# Sheet1_1.net
KiCad netlist of a schematic drawn in Altium Designer
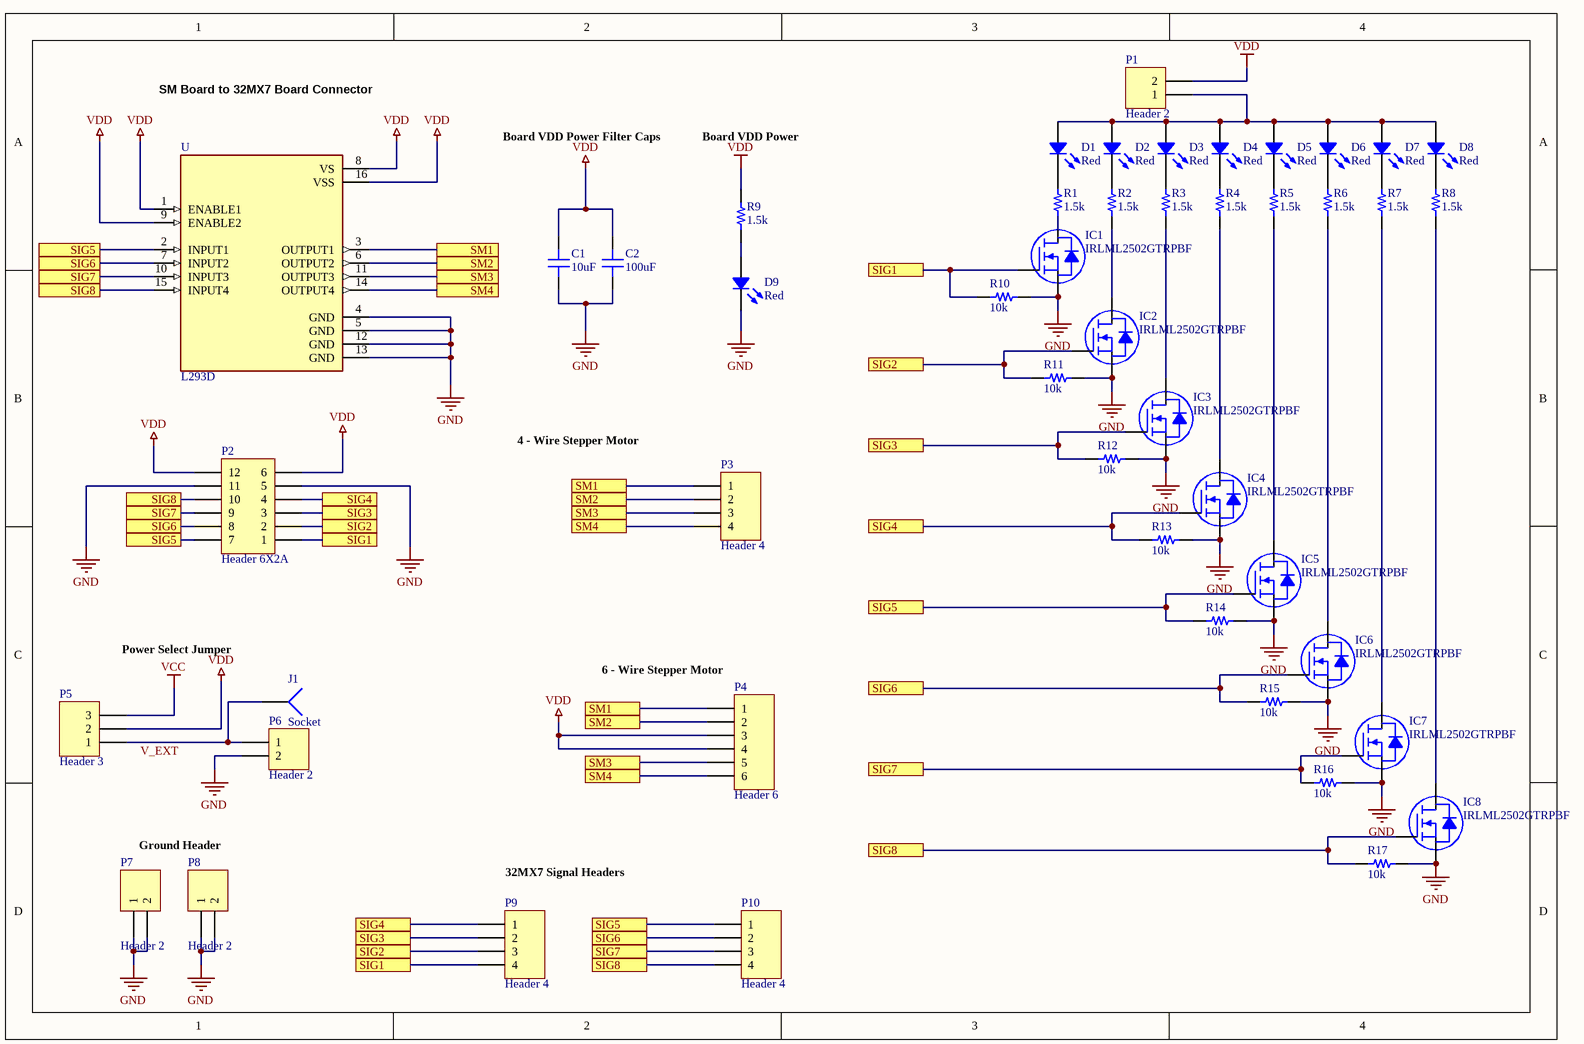
[diagram p0: Sheet1 (1).SchDoc]

(export (version "E")
  (design (tool "Eeschema 10.0.6"))
  (components
    (comp (ref "C1")
      (value "10uF")
      (footprint "CAP 1206/3216")
      (description "CAP CER 10UF 16V X5R 1206")
      (fields
        (field (name "PART NUMBER") "CL31A106KOCLNNC")
        (field (name "MANUFACTURER") "Samsung Electro-Mechanics America, Inc.")
      )
      (libsource (lib "Capacitor - Ceramic - Sumsung") (part "CL31A106KOCLNNC"))
    )
    (comp (ref "C2")
      (value "100uF")
      (footprint "CAP 1206/3216")
      (description "CAP CER 100UF 6.3V X5R 1206")
      (fields
        (field (name "PART NUMBER") "CL31A107MQHNNNE")
        (field (name "MANUFACTURER") "Samsung Electro-Mechanics America, Inc.")
      )
      (libsource (lib "Capacitor - Ceramic - Sumsung") (part "CL31A107MQHNNNE"))
    )
    (comp (ref "D1")
      (value "Red")
      (footprint "LED 1206/3216 RED")
      (description "LED RED CLEAR 1206 SMD")
      (fields (field (name "PART NUMBER") "SM1206NHC-IL") (field (name "MANUFACTURER") "Bivar Inc."))
      (libsource (lib "Chip LED") (part "SM1206NHC-IL"))
    )
    (comp (ref "D2")
      (value "Red")
      (footprint "LED 1206/3216 RED")
      (description "LED RED CLEAR 1206 SMD")
      (fields (field (name "PART NUMBER") "SM1206NHC-IL") (field (name "MANUFACTURER") "Bivar Inc."))
      (libsource (lib "Chip LED") (part "SM1206NHC-IL"))
    )
    (comp (ref "D3")
      (value "Red")
      (footprint "LED 1206/3216 RED")
      (description "LED RED CLEAR 1206 SMD")
      (fields (field (name "PART NUMBER") "SM1206NHC-IL") (field (name "MANUFACTURER") "Bivar Inc."))
      (libsource (lib "Chip LED") (part "SM1206NHC-IL"))
    )
    (comp (ref "D4")
      (value "Red")
      (footprint "LED 1206/3216 RED")
      (description "LED RED CLEAR 1206 SMD")
      (fields (field (name "PART NUMBER") "SM1206NHC-IL") (field (name "MANUFACTURER") "Bivar Inc."))
      (libsource (lib "Chip LED") (part "SM1206NHC-IL"))
    )
    (comp (ref "D5")
      (value "Red")
      (footprint "LED 1206/3216 RED")
      (description "LED RED CLEAR 1206 SMD")
      (fields (field (name "PART NUMBER") "SM1206NHC-IL") (field (name "MANUFACTURER") "Bivar Inc."))
      (libsource (lib "Chip LED") (part "SM1206NHC-IL"))
    )
    (comp (ref "D6")
      (value "Red")
      (footprint "LED 1206/3216 RED")
      (description "LED RED CLEAR 1206 SMD")
      (fields (field (name "PART NUMBER") "SM1206NHC-IL") (field (name "MANUFACTURER") "Bivar Inc."))
      (libsource (lib "Chip LED") (part "SM1206NHC-IL"))
    )
    (comp (ref "D7")
      (value "Red")
      (footprint "LED 1206/3216 RED")
      (description "LED RED CLEAR 1206 SMD")
      (fields (field (name "PART NUMBER") "SM1206NHC-IL") (field (name "MANUFACTURER") "Bivar Inc."))
      (libsource (lib "Chip LED") (part "SM1206NHC-IL"))
    )
    (comp (ref "D8")
      (value "Red")
      (footprint "LED 1206/3216 RED")
      (description "LED RED CLEAR 1206 SMD")
      (fields (field (name "PART NUMBER") "SM1206NHC-IL") (field (name "MANUFACTURER") "Bivar Inc."))
      (libsource (lib "Chip LED") (part "SM1206NHC-IL"))
    )
    (comp (ref "D9")
      (value "Red")
      (footprint "LED 1206/3216 RED")
      (description "LED RED CLEAR 1206 SMD")
      (fields (field (name "PART NUMBER") "SM1206NHC-IL") (field (name "MANUFACTURER") "Bivar Inc."))
      (libsource (lib "Chip LED") (part "SM1206NHC-IL"))
    )
    (comp (ref "IC1")
      (value "IRLML2502GTRPBF")
      (footprint "INFINEON SOT-23-3")
      (description "MOSFET N-CH 20V 4.2A SOT-23-3")
      (fields (field (name "MANUFACTURER") "Infineon Technologies"))
      (libsource (lib "N-Channel FET") (part "IRLML2502GTRPBF"))
    )
    (comp (ref "IC2")
      (value "IRLML2502GTRPBF")
      (footprint "INFINEON SOT-23-3")
      (description "MOSFET N-CH 20V 4.2A SOT-23-3")
      (fields (field (name "MANUFACTURER") "Infineon Technologies"))
      (libsource (lib "N-Channel FET") (part "IRLML2502GTRPBF"))
    )
    (comp (ref "IC3")
      (value "IRLML2502GTRPBF")
      (footprint "INFINEON SOT-23-3")
      (description "MOSFET N-CH 20V 4.2A SOT-23-3")
      (fields (field (name "MANUFACTURER") "Infineon Technologies"))
      (libsource (lib "N-Channel FET") (part "IRLML2502GTRPBF"))
    )
    (comp (ref "IC4")
      (value "IRLML2502GTRPBF")
      (footprint "INFINEON SOT-23-3")
      (description "MOSFET N-CH 20V 4.2A SOT-23-3")
      (fields (field (name "MANUFACTURER") "Infineon Technologies"))
      (libsource (lib "N-Channel FET") (part "IRLML2502GTRPBF"))
    )
    (comp (ref "IC5")
      (value "IRLML2502GTRPBF")
      (footprint "INFINEON SOT-23-3")
      (description "MOSFET N-CH 20V 4.2A SOT-23-3")
      (fields (field (name "MANUFACTURER") "Infineon Technologies"))
      (libsource (lib "N-Channel FET") (part "IRLML2502GTRPBF"))
    )
    (comp (ref "IC6")
      (value "IRLML2502GTRPBF")
      (footprint "INFINEON SOT-23-3")
      (description "MOSFET N-CH 20V 4.2A SOT-23-3")
      (fields (field (name "MANUFACTURER") "Infineon Technologies"))
      (libsource (lib "N-Channel FET") (part "IRLML2502GTRPBF"))
    )
    (comp (ref "IC7")
      (value "IRLML2502GTRPBF")
      (footprint "INFINEON SOT-23-3")
      (description "MOSFET N-CH 20V 4.2A SOT-23-3")
      (fields (field (name "MANUFACTURER") "Infineon Technologies"))
      (libsource (lib "N-Channel FET") (part "IRLML2502GTRPBF"))
    )
    (comp (ref "IC8")
      (value "IRLML2502GTRPBF")
      (footprint "INFINEON SOT-23-3")
      (description "MOSFET N-CH 20V 4.2A SOT-23-3")
      (fields (field (name "MANUFACTURER") "Infineon Technologies"))
      (libsource (lib "N-Channel FET") (part "IRLML2502GTRPBF"))
    )
    (comp (ref "J1")
      (value "Socket")
      (footprint "PIN1")
      (fields (field (name "PUBLISHER") "Altium Limited"))
      (libsource (lib "Miscellaneous Connectors") (part "Socket"))
    )
    (comp (ref "P1")
      (value "Header 2")
      (footprint "HDR1X2")
      (description "Header, 2-Pin")
      (fields (field (name "PUBLISHER") "Altium Limited"))
      (libsource (lib "") (part "Header 2_2"))
    )
    (comp (ref "P2")
      (value "Header 6X2A")
      (footprint "HDR2X6_CEN")
      (description "Header, 6-Pin, Dual row")
      (fields (field (name "PUBLISHER") "Altium Limited"))
      (libsource (lib "Miscellaneous Connectors") (part "Header 6X2A"))
    )
    (comp (ref "P3")
      (value "Header 4")
      (footprint "HDR1X4")
      (description "Header, 4-Pin")
      (fields (field (name "PUBLISHER") "Altium Limited"))
      (libsource (lib "Miscellaneous Connectors") (part "Header 4"))
    )
    (comp (ref "P4")
      (value "Header 6")
      (footprint "HDR1X6")
      (description "Header, 6-Pin")
      (fields (field (name "PUBLISHER") "Altium Limited"))
      (libsource (lib "Miscellaneous Connectors") (part "Header 6"))
    )
    (comp (ref "P5")
      (value "Header 3")
      (footprint "HDR1X3")
      (description "Header, 3-Pin")
      (fields (field (name "PUBLISHER") "Altium Limited"))
      (libsource (lib "Miscellaneous Connectors") (part "Header 3"))
    )
    (comp (ref "P6")
      (value "Header 2")
      (footprint "HDR1X2")
      (description "Header, 2-Pin")
      (fields (field (name "PUBLISHER") "Altium Limited"))
      (libsource (lib "") (part "Header 2_1"))
    )
    (comp (ref "P7")
      (value "Header 2")
      (footprint "HDR1X2")
      (description "Header, 2-Pin")
      (fields (field (name "PUBLISHER") "Altium Limited"))
      (libsource (lib "Miscellaneous Connectors") (part "Header 2"))
    )
    (comp (ref "P8")
      (value "Header 2")
      (footprint "HDR1X2")
      (description "Header, 2-Pin")
      (fields (field (name "PUBLISHER") "Altium Limited"))
      (libsource (lib "Miscellaneous Connectors") (part "Header 2"))
    )
    (comp (ref "P9")
      (value "Header 4")
      (footprint "HDR1X4")
      (description "Header, 4-Pin")
      (fields (field (name "PUBLISHER") "Altium Limited"))
      (libsource (lib "Miscellaneous Connectors") (part "Header 4"))
    )
    (comp (ref "P10")
      (value "Header 4")
      (footprint "HDR1X4")
      (description "Header, 4-Pin")
      (fields (field (name "PUBLISHER") "Altium Limited"))
      (libsource (lib "Miscellaneous Connectors") (part "Header 4"))
    )
    (comp (ref "R1")
      (value "1.5k")
      (footprint "RES 1206/3216")
      (description "RES SMD 1.5K OHM 1% 1/4W 1206")
      (fields
        (field (name "PART NUMBER") "ERJ-8ENF1501V")
        (field (name "MANUFACTURER") "Panasonic Electronic Components")
      )
      (libsource (lib "Resistor - Chip") (part "ERJ-8ENF1501V"))
    )
    (comp (ref "R2")
      (value "1.5k")
      (footprint "RES 1206/3216")
      (description "RES SMD 1.5K OHM 1% 1/4W 1206")
      (fields
        (field (name "PART NUMBER") "ERJ-8ENF1501V")
        (field (name "MANUFACTURER") "Panasonic Electronic Components")
      )
      (libsource (lib "Resistor - Chip") (part "ERJ-8ENF1501V"))
    )
    (comp (ref "R3")
      (value "1.5k")
      (footprint "RES 1206/3216")
      (description "RES SMD 1.5K OHM 1% 1/4W 1206")
      (fields
        (field (name "PART NUMBER") "ERJ-8ENF1501V")
        (field (name "MANUFACTURER") "Panasonic Electronic Components")
      )
      (libsource (lib "Resistor - Chip") (part "ERJ-8ENF1501V"))
    )
    (comp (ref "R4")
      (value "1.5k")
      (footprint "RES 1206/3216")
      (description "RES SMD 1.5K OHM 1% 1/4W 1206")
      (fields
        (field (name "PART NUMBER") "ERJ-8ENF1501V")
        (field (name "MANUFACTURER") "Panasonic Electronic Components")
      )
      (libsource (lib "Resistor - Chip") (part "ERJ-8ENF1501V"))
    )
    (comp (ref "R5")
      (value "1.5k")
      (footprint "RES 1206/3216")
      (description "RES SMD 1.5K OHM 1% 1/4W 1206")
      (fields
        (field (name "PART NUMBER") "ERJ-8ENF1501V")
        (field (name "MANUFACTURER") "Panasonic Electronic Components")
      )
      (libsource (lib "Resistor - Chip") (part "ERJ-8ENF1501V"))
    )
    (comp (ref "R6")
      (value "1.5k")
      (footprint "RES 1206/3216")
      (description "RES SMD 1.5K OHM 1% 1/4W 1206")
      (fields
        (field (name "PART NUMBER") "ERJ-8ENF1501V")
        (field (name "MANUFACTURER") "Panasonic Electronic Components")
      )
      (libsource (lib "Resistor - Chip") (part "ERJ-8ENF1501V"))
    )
    (comp (ref "R7")
      (value "1.5k")
      (footprint "RES 1206/3216")
      (description "RES SMD 1.5K OHM 1% 1/4W 1206")
      (fields
        (field (name "PART NUMBER") "ERJ-8ENF1501V")
        (field (name "MANUFACTURER") "Panasonic Electronic Components")
      )
      (libsource (lib "Resistor - Chip") (part "ERJ-8ENF1501V"))
    )
    (comp (ref "R8")
      (value "1.5k")
      (footprint "RES 1206/3216")
      (description "RES SMD 1.5K OHM 1% 1/4W 1206")
      (fields
        (field (name "PART NUMBER") "ERJ-8ENF1501V")
        (field (name "MANUFACTURER") "Panasonic Electronic Components")
      )
      (libsource (lib "Resistor - Chip") (part "ERJ-8ENF1501V"))
    )
    (comp (ref "R9")
      (value "1.5k")
      (footprint "RES 1206/3216")
      (description "RES SMD 1.5K OHM 1% 1/4W 1206")
      (fields
        (field (name "PART NUMBER") "ERJ-8ENF1501V")
        (field (name "MANUFACTURER") "Panasonic Electronic Components")
      )
      (libsource (lib "Resistor - Chip") (part "ERJ-8ENF1501V"))
    )
    (comp (ref "R10")
      (value "10k")
      (footprint "RES 1206/3216")
      (description "RES SMD 10K OHM 1% 1/4W 1206")
      (fields
        (field (name "PART NUMBER") "ERJ-8ENF1002V")
        (field (name "MANUFACTURER") "Panasonic Electronic Components")
      )
      (libsource (lib "Resistor - Chip") (part "ERJ-8ENF1002V"))
    )
    (comp (ref "R11")
      (value "10k")
      (footprint "RES 1206/3216")
      (description "RES SMD 10K OHM 1% 1/4W 1206")
      (fields
        (field (name "PART NUMBER") "ERJ-8ENF1002V")
        (field (name "MANUFACTURER") "Panasonic Electronic Components")
      )
      (libsource (lib "Resistor - Chip") (part "ERJ-8ENF1002V"))
    )
    (comp (ref "R12")
      (value "10k")
      (footprint "RES 1206/3216")
      (description "RES SMD 10K OHM 1% 1/4W 1206")
      (fields
        (field (name "PART NUMBER") "ERJ-8ENF1002V")
        (field (name "MANUFACTURER") "Panasonic Electronic Components")
      )
      (libsource (lib "Resistor - Chip") (part "ERJ-8ENF1002V"))
    )
    (comp (ref "R13")
      (value "10k")
      (footprint "RES 1206/3216")
      (description "RES SMD 10K OHM 1% 1/4W 1206")
      (fields
        (field (name "PART NUMBER") "ERJ-8ENF1002V")
        (field (name "MANUFACTURER") "Panasonic Electronic Components")
      )
      (libsource (lib "Resistor - Chip") (part "ERJ-8ENF1002V"))
    )
    (comp (ref "R14")
      (value "10k")
      (footprint "RES 1206/3216")
      (description "RES SMD 10K OHM 1% 1/4W 1206")
      (fields
        (field (name "PART NUMBER") "ERJ-8ENF1002V")
        (field (name "MANUFACTURER") "Panasonic Electronic Components")
      )
      (libsource (lib "Resistor - Chip") (part "ERJ-8ENF1002V"))
    )
    (comp (ref "R15")
      (value "10k")
      (footprint "RES 1206/3216")
      (description "RES SMD 10K OHM 1% 1/4W 1206")
      (fields
        (field (name "PART NUMBER") "ERJ-8ENF1002V")
        (field (name "MANUFACTURER") "Panasonic Electronic Components")
      )
      (libsource (lib "Resistor - Chip") (part "ERJ-8ENF1002V"))
    )
    (comp (ref "R16")
      (value "10k")
      (footprint "RES 1206/3216")
      (description "RES SMD 10K OHM 1% 1/4W 1206")
      (fields
        (field (name "PART NUMBER") "ERJ-8ENF1002V")
        (field (name "MANUFACTURER") "Panasonic Electronic Components")
      )
      (libsource (lib "Resistor - Chip") (part "ERJ-8ENF1002V"))
    )
    (comp (ref "R17")
      (value "10k")
      (footprint "RES 1206/3216")
      (description "RES SMD 10K OHM 1% 1/4W 1206")
      (fields
        (field (name "PART NUMBER") "ERJ-8ENF1002V")
        (field (name "MANUFACTURER") "Panasonic Electronic Components")
      )
      (libsource (lib "Resistor - Chip") (part "ERJ-8ENF1002V"))
    )
    (comp (ref "U")
      (value "L293D")
      (footprint "DIP880W50P254L2000H510Q16")
      (description "Bipolar Motor Driver Parallel 16-PowerDIP")
      (fields (field (name "MF") "STMicroelectronics"))
      (libsource (lib "L293D") (part "L293D"))
    )
  )
  (nets
    (net (code "1") (name "/SIG1") (class "Default")
      (node (ref "IC1") (pin "1") (pinfunction "G_1") (pintype "passive"))
      (node (ref "P2") (pin "1") (pinfunction "1_1") (pintype "passive"))
      (node (ref "P9") (pin "4") (pinfunction "4_4") (pintype "passive"))
      (node (ref "R10") (pin "1") (pinfunction "1_1") (pintype "passive"))
    )
    (net (code "2") (name "/SIG2") (class "Default")
      (node (ref "IC2") (pin "1") (pinfunction "G_1") (pintype "passive"))
      (node (ref "P2") (pin "2") (pinfunction "2_2") (pintype "passive"))
      (node (ref "P9") (pin "3") (pinfunction "3_3") (pintype "passive"))
      (node (ref "R11") (pin "1") (pinfunction "1_1") (pintype "passive"))
    )
    (net (code "3") (name "/SIG3") (class "Default")
      (node (ref "IC3") (pin "1") (pinfunction "G_1") (pintype "passive"))
      (node (ref "P2") (pin "3") (pinfunction "3_3") (pintype "passive"))
      (node (ref "P9") (pin "2") (pinfunction "2_2") (pintype "passive"))
      (node (ref "R12") (pin "1") (pinfunction "1_1") (pintype "passive"))
    )
    (net (code "4") (name "/SIG4") (class "Default")
      (node (ref "IC4") (pin "1") (pinfunction "G_1") (pintype "passive"))
      (node (ref "P2") (pin "4") (pinfunction "4_4") (pintype "passive"))
      (node (ref "P9") (pin "1") (pinfunction "1_1") (pintype "passive"))
      (node (ref "R13") (pin "1") (pinfunction "1_1") (pintype "passive"))
    )
    (net (code "5") (name "/SIG5") (class "Default")
      (node (ref "IC5") (pin "1") (pinfunction "G_1") (pintype "passive"))
      (node (ref "P10") (pin "1") (pinfunction "1_1") (pintype "passive"))
      (node (ref "P2") (pin "7") (pinfunction "7_7") (pintype "passive"))
      (node (ref "R14") (pin "1") (pinfunction "1_1") (pintype "passive"))
      (node (ref "U") (pin "2") (pinfunction "INPUT1_2") (pintype "input"))
    )
    (net (code "6") (name "/SIG6") (class "Default")
      (node (ref "IC6") (pin "1") (pinfunction "G_1") (pintype "passive"))
      (node (ref "P10") (pin "2") (pinfunction "2_2") (pintype "passive"))
      (node (ref "P2") (pin "8") (pinfunction "8_8") (pintype "passive"))
      (node (ref "R15") (pin "1") (pinfunction "1_1") (pintype "passive"))
      (node (ref "U") (pin "7") (pinfunction "INPUT2_7") (pintype "input"))
    )
    (net (code "7") (name "/SIG7") (class "Default")
      (node (ref "IC7") (pin "1") (pinfunction "G_1") (pintype "passive"))
      (node (ref "P10") (pin "3") (pinfunction "3_3") (pintype "passive"))
      (node (ref "P2") (pin "9") (pinfunction "9_9") (pintype "passive"))
      (node (ref "R16") (pin "1") (pinfunction "1_1") (pintype "passive"))
      (node (ref "U") (pin "10") (pinfunction "INPUT3_10") (pintype "input"))
    )
    (net (code "8") (name "/SIG8") (class "Default")
      (node (ref "IC8") (pin "1") (pinfunction "G_1") (pintype "passive"))
      (node (ref "P10") (pin "4") (pinfunction "4_4") (pintype "passive"))
      (node (ref "P2") (pin "10") (pinfunction "10_10") (pintype "passive"))
      (node (ref "R17") (pin "1") (pinfunction "1_1") (pintype "passive"))
      (node (ref "U") (pin "15") (pinfunction "INPUT4_15") (pintype "input"))
    )
    (net (code "9") (name "/SM1") (class "Default")
      (node (ref "P3") (pin "1") (pinfunction "1_1") (pintype "passive"))
      (node (ref "P4") (pin "1") (pinfunction "1_1") (pintype "passive"))
      (node (ref "U") (pin "3") (pinfunction "OUTPUT1_3") (pintype "output"))
    )
    (net (code "10") (name "/SM2") (class "Default")
      (node (ref "P3") (pin "2") (pinfunction "2_2") (pintype "passive"))
      (node (ref "P4") (pin "2") (pinfunction "2_2") (pintype "passive"))
      (node (ref "U") (pin "6") (pinfunction "OUTPUT2_6") (pintype "output"))
    )
    (net (code "11") (name "/SM3") (class "Default")
      (node (ref "P3") (pin "3") (pinfunction "3_3") (pintype "passive"))
      (node (ref "P4") (pin "5") (pinfunction "5_5") (pintype "passive"))
      (node (ref "U") (pin "11") (pinfunction "OUTPUT3_11") (pintype "output"))
    )
    (net (code "12") (name "/SM4") (class "Default")
      (node (ref "P3") (pin "4") (pinfunction "4_4") (pintype "passive"))
      (node (ref "P4") (pin "6") (pinfunction "6_6") (pintype "passive"))
      (node (ref "U") (pin "14") (pinfunction "OUTPUT4_14") (pintype "output"))
    )
    (net (code "13") (name "/V_EXT") (class "Default")
      (node (ref "J1") (pin "1") (pinfunction "1_1") (pintype "passive"))
      (node (ref "P5") (pin "1") (pinfunction "1_1") (pintype "passive"))
      (node (ref "P6") (pin "1") (pinfunction "1_1") (pintype "passive"))
    )
    (net (code "14") (name "GND") (class "Default")
      (node (ref "C1") (pin "1") (pinfunction "1_1") (pintype "passive"))
      (node (ref "C2") (pin "1") (pinfunction "1_1") (pintype "passive"))
      (node (ref "D9") (pin "2") (pinfunction "2_2") (pintype "passive"))
      (node (ref "IC1") (pin "3") (pinfunction "S_3") (pintype "passive"))
      (node (ref "IC2") (pin "3") (pinfunction "S_3") (pintype "passive"))
      (node (ref "IC3") (pin "3") (pinfunction "S_3") (pintype "passive"))
      (node (ref "IC4") (pin "3") (pinfunction "S_3") (pintype "passive"))
      (node (ref "IC5") (pin "3") (pinfunction "S_3") (pintype "passive"))
      (node (ref "IC6") (pin "3") (pinfunction "S_3") (pintype "passive"))
      (node (ref "IC7") (pin "3") (pinfunction "S_3") (pintype "passive"))
      (node (ref "IC8") (pin "3") (pinfunction "S_3") (pintype "passive"))
      (node (ref "P2") (pin "11") (pinfunction "11_11") (pintype "passive"))
      (node (ref "P2") (pin "5") (pinfunction "5_5") (pintype "passive"))
      (node (ref "P6") (pin "2") (pinfunction "2_2") (pintype "passive"))
      (node (ref "P7") (pin "1") (pinfunction "1_1") (pintype "passive"))
      (node (ref "P7") (pin "2") (pinfunction "2_2") (pintype "passive"))
      (node (ref "P8") (pin "1") (pinfunction "1_1") (pintype "passive"))
      (node (ref "P8") (pin "2") (pinfunction "2_2") (pintype "passive"))
      (node (ref "R10") (pin "2") (pinfunction "2_2") (pintype "passive"))
      (node (ref "R11") (pin "2") (pinfunction "2_2") (pintype "passive"))
      (node (ref "R12") (pin "2") (pinfunction "2_2") (pintype "passive"))
      (node (ref "R13") (pin "2") (pinfunction "2_2") (pintype "passive"))
      (node (ref "R14") (pin "2") (pinfunction "2_2") (pintype "passive"))
      (node (ref "R15") (pin "2") (pinfunction "2_2") (pintype "passive"))
      (node (ref "R16") (pin "2") (pinfunction "2_2") (pintype "passive"))
      (node (ref "R17") (pin "2") (pinfunction "2_2") (pintype "passive"))
      (node (ref "U") (pin "12") (pinfunction "GND_12") (pintype "power_in"))
      (node (ref "U") (pin "13") (pinfunction "GND_13") (pintype "power_in"))
      (node (ref "U") (pin "4") (pinfunction "GND_4") (pintype "power_in"))
      (node (ref "U") (pin "5") (pinfunction "GND_5") (pintype "power_in"))
    )
    (net (code "15") (name "Net-(D1-Pad1)") (class "Default")
      (node (ref "D1") (pin "1") (pinfunction "1_1") (pintype "passive"))
      (node (ref "D2") (pin "1") (pinfunction "1_1") (pintype "passive"))
      (node (ref "D3") (pin "1") (pinfunction "1_1") (pintype "passive"))
      (node (ref "D4") (pin "1") (pinfunction "1_1") (pintype "passive"))
      (node (ref "D5") (pin "1") (pinfunction "1_1") (pintype "passive"))
      (node (ref "D6") (pin "1") (pinfunction "1_1") (pintype "passive"))
      (node (ref "D7") (pin "1") (pinfunction "1_1") (pintype "passive"))
      (node (ref "D8") (pin "1") (pinfunction "1_1") (pintype "passive"))
      (node (ref "P1") (pin "1") (pinfunction "1_1") (pintype "passive"))
    )
    (net (code "16") (name "Net-(D1-Pad2)") (class "Default")
      (node (ref "D1") (pin "2") (pinfunction "2_2") (pintype "passive"))
      (node (ref "R1") (pin "2") (pinfunction "2_2") (pintype "passive"))
    )
    (net (code "17") (name "Net-(D2-Pad2)") (class "Default")
      (node (ref "D2") (pin "2") (pinfunction "2_2") (pintype "passive"))
      (node (ref "R2") (pin "2") (pinfunction "2_2") (pintype "passive"))
    )
    (net (code "18") (name "Net-(D3-Pad2)") (class "Default")
      (node (ref "D3") (pin "2") (pinfunction "2_2") (pintype "passive"))
      (node (ref "R3") (pin "2") (pinfunction "2_2") (pintype "passive"))
    )
    (net (code "19") (name "Net-(D4-Pad2)") (class "Default")
      (node (ref "D4") (pin "2") (pinfunction "2_2") (pintype "passive"))
      (node (ref "R4") (pin "2") (pinfunction "2_2") (pintype "passive"))
    )
    (net (code "20") (name "Net-(D5-Pad2)") (class "Default")
      (node (ref "D5") (pin "2") (pinfunction "2_2") (pintype "passive"))
      (node (ref "R5") (pin "2") (pinfunction "2_2") (pintype "passive"))
    )
    (net (code "21") (name "Net-(D6-Pad2)") (class "Default")
      (node (ref "D6") (pin "2") (pinfunction "2_2") (pintype "passive"))
      (node (ref "R6") (pin "2") (pinfunction "2_2") (pintype "passive"))
    )
    (net (code "22") (name "Net-(D7-Pad2)") (class "Default")
      (node (ref "D7") (pin "2") (pinfunction "2_2") (pintype "passive"))
      (node (ref "R7") (pin "2") (pinfunction "2_2") (pintype "passive"))
    )
    (net (code "23") (name "Net-(D8-Pad2)") (class "Default")
      (node (ref "D8") (pin "2") (pinfunction "2_2") (pintype "passive"))
      (node (ref "R8") (pin "2") (pinfunction "2_2") (pintype "passive"))
    )
    (net (code "24") (name "Net-(D9-Pad1)") (class "Default")
      (node (ref "D9") (pin "1") (pinfunction "1_1") (pintype "passive"))
      (node (ref "R9") (pin "1") (pinfunction "1_1") (pintype "passive"))
    )
    (net (code "25") (name "Net-(IC1-D)") (class "Default")
      (node (ref "IC1") (pin "2") (pinfunction "D_2") (pintype "passive"))
      (node (ref "R1") (pin "1") (pinfunction "1_1") (pintype "passive"))
    )
    (net (code "26") (name "Net-(IC2-D)") (class "Default")
      (node (ref "IC2") (pin "2") (pinfunction "D_2") (pintype "passive"))
      (node (ref "R2") (pin "1") (pinfunction "1_1") (pintype "passive"))
    )
    (net (code "27") (name "Net-(IC3-D)") (class "Default")
      (node (ref "IC3") (pin "2") (pinfunction "D_2") (pintype "passive"))
      (node (ref "R3") (pin "1") (pinfunction "1_1") (pintype "passive"))
    )
    (net (code "28") (name "Net-(IC4-D)") (class "Default")
      (node (ref "IC4") (pin "2") (pinfunction "D_2") (pintype "passive"))
      (node (ref "R4") (pin "1") (pinfunction "1_1") (pintype "passive"))
    )
    (net (code "29") (name "Net-(IC5-D)") (class "Default")
      (node (ref "IC5") (pin "2") (pinfunction "D_2") (pintype "passive"))
      (node (ref "R5") (pin "1") (pinfunction "1_1") (pintype "passive"))
    )
    (net (code "30") (name "Net-(IC6-D)") (class "Default")
      (node (ref "IC6") (pin "2") (pinfunction "D_2") (pintype "passive"))
      (node (ref "R6") (pin "1") (pinfunction "1_1") (pintype "passive"))
    )
    (net (code "31") (name "Net-(IC7-D)") (class "Default")
      (node (ref "IC7") (pin "2") (pinfunction "D_2") (pintype "passive"))
      (node (ref "R7") (pin "1") (pinfunction "1_1") (pintype "passive"))
    )
    (net (code "32") (name "Net-(IC8-D)") (class "Default")
      (node (ref "IC8") (pin "2") (pinfunction "D_2") (pintype "passive"))
      (node (ref "R8") (pin "1") (pinfunction "1_1") (pintype "passive"))
    )
    (net (code "33") (name "VCC") (class "Default")
      (node (ref "P5") (pin "3") (pinfunction "3_3") (pintype "passive"))
    )
    (net (code "34") (name "VDD") (class "Default")
      (node (ref "C1") (pin "2") (pinfunction "2_2") (pintype "passive"))
      (node (ref "C2") (pin "2") (pinfunction "2_2") (pintype "passive"))
      (node (ref "P1") (pin "2") (pinfunction "2_2") (pintype "passive"))
      (node (ref "P2") (pin "12") (pinfunction "12_12") (pintype "passive"))
      (node (ref "P2") (pin "6") (pinfunction "6_6") (pintype "passive"))
      (node (ref "P4") (pin "3") (pinfunction "3_3") (pintype "passive"))
      (node (ref "P4") (pin "4") (pinfunction "4_4") (pintype "passive"))
      (node (ref "P5") (pin "2") (pinfunction "2_2") (pintype "passive"))
      (node (ref "R9") (pin "2") (pinfunction "2_2") (pintype "passive"))
      (node (ref "U") (pin "1") (pinfunction "ENABLE1_1") (pintype "input"))
      (node (ref "U") (pin "16") (pinfunction "VSS_16") (pintype "power_in"))
      (node (ref "U") (pin "8") (pinfunction "VS_8") (pintype "power_in"))
      (node (ref "U") (pin "9") (pinfunction "ENABLE2_9") (pintype "input"))
    )
  )
)
